# pedal.net
KiCad netlist of a schematic drawn in Altium Designer
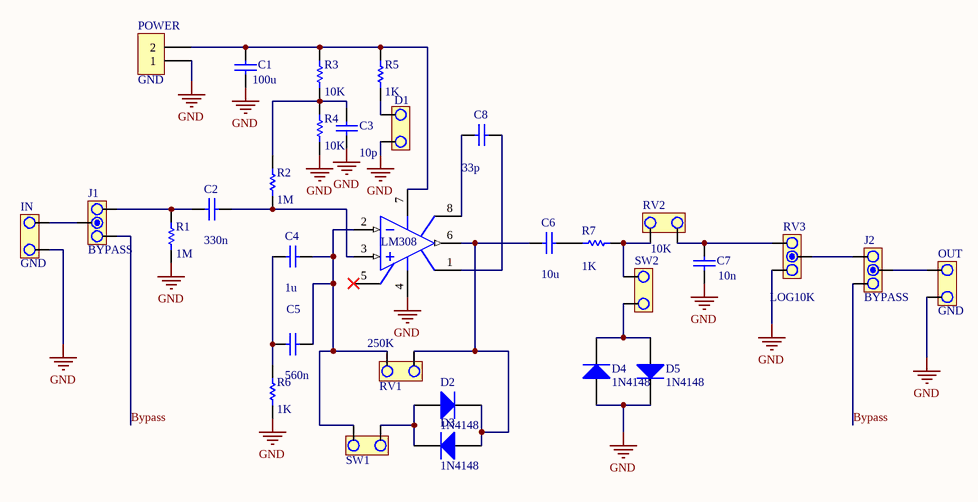
[diagram p0: pedal.SchDoc]

(export (version "E")
  (design (tool "Eeschema 10.0.6"))
  (components
    (comp (ref "C1")
      (value "100u")
      (footprint "CAP200")
      (description "Capacitor")
      (fields (field (name "PUBLISHER") "Altium Limited"))
      (libsource (lib "Miscellaneous Devices") (part "Cap"))
    )
    (comp (ref "C2")
      (value "330n")
      (footprint "CAP200")
      (description "Capacitor")
      (fields (field (name "PUBLISHER") "Altium Limited"))
      (libsource (lib "Miscellaneous Devices") (part "Cap"))
    )
    (comp (ref "C3")
      (value "10p")
      (footprint "CAP200")
      (description "Capacitor")
      (fields (field (name "PUBLISHER") "Altium Limited"))
      (libsource (lib "Miscellaneous Devices") (part "Cap"))
    )
    (comp (ref "C4")
      (value "1u")
      (footprint "CAP200")
      (description "Capacitor")
      (fields (field (name "PUBLISHER") "Altium Limited"))
      (libsource (lib "Miscellaneous Devices") (part "Cap"))
    )
    (comp (ref "C5")
      (value "560n")
      (footprint "RAD-0.3")
      (description "Capacitor")
      (fields (field (name "PUBLISHER") "Altium Limited"))
      (libsource (lib "Miscellaneous Devices") (part "Cap"))
    )
    (comp (ref "C6")
      (value "10u")
      (footprint "CAP200")
      (description "Capacitor")
      (fields (field (name "PUBLISHER") "Altium Limited"))
      (libsource (lib "Miscellaneous Devices") (part "Cap"))
    )
    (comp (ref "C7")
      (value "10n")
      (footprint "CAP200")
      (description "Capacitor")
      (fields (field (name "PUBLISHER") "Altium Limited"))
      (libsource (lib "Miscellaneous Devices") (part "Cap"))
    )
    (comp (ref "C8")
      (value "33p")
      (footprint "CAP200")
      (fields (field (name "PUBLISHER") "Altium Limited"))
      (libsource (lib "Miscellaneous Devices") (part "Cap"))
    )
    (comp (ref "D1") (value "~") (footprint "JUMPER2") (libsource (lib "") (part "JUMPER_1")))
    (comp (ref "D2")
      (value "1N4148")
      (footprint "DO-35")
      (description "High Conductance Fast Diode")
      (fields (field (name "PUBLISHER") "Altium Limited"))
      (libsource (lib "Miscellaneous Devices") (part "Diode 1N4148"))
    )
    (comp (ref "D3")
      (value "1N4148")
      (footprint "DO-35")
      (description "High Conductance Fast Diode")
      (fields (field (name "PUBLISHER") "Altium Limited"))
      (libsource (lib "Miscellaneous Devices") (part "Diode 1N4148"))
    )
    (comp (ref "D4")
      (value "1N4148")
      (footprint "DO-35")
      (description "High Conductance Fast Diode")
      (fields (field (name "PUBLISHER") "Altium Limited"))
      (libsource (lib "Miscellaneous Devices") (part "Diode 1N4148"))
    )
    (comp (ref "D5")
      (value "1N4148")
      (footprint "DO-35")
      (description "High Conductance Fast Diode")
      (fields (field (name "PUBLISHER") "Altium Limited"))
      (libsource (lib "Miscellaneous Devices") (part "Diode 1N4148"))
    )
    (comp (ref "IN") (value "GND") (footprint "JUMPER2") (libsource (lib "LIB PIO IX") (part "JUMPER")))
    (comp (ref "J1") (value "BYPASS") (footprint "JUMPER3") (libsource (lib "LIB PIO IX") (part "JUMPER3")))
    (comp (ref "J2") (value "BYPASS") (footprint "JUMPER3") (libsource (lib "") (part "JUMPER3_1")))
    (comp (ref "LM308")
      (value "~")
      (footprint "DIP8")
      (description "FET Operational Amplifier")
      (fields (field (name "PUBLISHER") "Altium Limited"))
      (libsource (lib "Miscellaneous Devices") (part "Op Amp"))
    )
    (comp (ref "OUT") (value "GND") (footprint "JUMPER2") (libsource (lib "") (part "JUMPER_1")))
    (comp (ref "POWER")
      (value "GND")
      (footprint "BORNERA2")
      (libsource (lib "LIB PIO IX") (part "BORNERA 2"))
    )
    (comp (ref "R1")
      (value "1M")
      (footprint "AXIAL-0.3")
      (description "Resistor")
      (fields (field (name "PUBLISHER") "Altium Limited"))
      (libsource (lib "Miscellaneous Devices") (part "Res1"))
    )
    (comp (ref "R2")
      (value "1M")
      (footprint "AXIAL-0.3")
      (description "Resistor")
      (fields (field (name "PUBLISHER") "Altium Limited"))
      (libsource (lib "Miscellaneous Devices") (part "Res1"))
    )
    (comp (ref "R3")
      (value "10K")
      (footprint "AXIAL-0.3")
      (description "Resistor")
      (fields (field (name "PUBLISHER") "Altium Limited"))
      (libsource (lib "Miscellaneous Devices") (part "Res1"))
    )
    (comp (ref "R4")
      (value "10K")
      (footprint "AXIAL-0.3")
      (description "Resistor")
      (fields (field (name "PUBLISHER") "Altium Limited"))
      (libsource (lib "Miscellaneous Devices") (part "Res1"))
    )
    (comp (ref "R5")
      (value "1K")
      (footprint "AXIAL-0.3")
      (description "Resistor")
      (fields (field (name "PUBLISHER") "Altium Limited"))
      (libsource (lib "Miscellaneous Devices") (part "Res1"))
    )
    (comp (ref "R6")
      (value "1K")
      (footprint "AXIAL-0.3")
      (description "Resistor")
      (fields (field (name "PUBLISHER") "Altium Limited"))
      (libsource (lib "Miscellaneous Devices") (part "Res1"))
    )
    (comp (ref "R7")
      (value "1K")
      (footprint "AXIAL-0.3")
      (description "Resistor")
      (fields (field (name "PUBLISHER") "Altium Limited"))
      (libsource (lib "Miscellaneous Devices") (part "Res1"))
    )
    (comp (ref "RV1") (value "250K") (footprint "JUMPER2") (libsource (lib "") (part "JUMPER_3")))
    (comp (ref "RV2") (value "10K") (footprint "JUMPER2") (libsource (lib "") (part "JUMPER_2")))
    (comp (ref "RV3") (value "LOG10K") (footprint "JUMPER3") (libsource (lib "") (part "JUMPER3_1")))
    (comp (ref "SW1") (value "~") (footprint "JUMPER2") (libsource (lib "") (part "JUMPER_3")))
    (comp (ref "SW2") (value "~") (footprint "JUMPER2") (libsource (lib "") (part "JUMPER_1")))
  )
  (nets
    (net (code "1") (name "/Bypass") (class "Default")
      (node (ref "J1") (pin "3") (pinfunction "3_3") (pintype "passive"))
      (node (ref "J2") (pin "1") (pinfunction "1_1") (pintype "passive"))
    )
    (net (code "2") (name "GND") (class "Default")
      (node (ref "C1") (pin "1") (pinfunction "1_1") (pintype "passive"))
      (node (ref "C3") (pin "1") (pinfunction "1_1") (pintype "passive"))
      (node (ref "C7") (pin "1") (pinfunction "1_1") (pintype "passive"))
      (node (ref "D1") (pin "1") (pinfunction "1_1") (pintype "passive"))
      (node (ref "D4") (pin "1") (pinfunction "A_1") (pintype "passive"))
      (node (ref "D5") (pin "2") (pinfunction "K_2") (pintype "passive"))
      (node (ref "IN") (pin "2") (pinfunction "2_2") (pintype "passive"))
      (node (ref "LM308") (pin "4") (pinfunction "V-_4") (pintype "power_in"))
      (node (ref "OUT") (pin "1") (pinfunction "1_1") (pintype "passive"))
      (node (ref "POWER") (pin "1") (pinfunction "1_1") (pintype "passive"))
      (node (ref "R1") (pin "1") (pinfunction "1_1") (pintype "passive"))
      (node (ref "R4") (pin "1") (pinfunction "1_1") (pintype "passive"))
      (node (ref "R6") (pin "1") (pinfunction "1_1") (pintype "passive"))
      (node (ref "RV3") (pin "1") (pinfunction "1_1") (pintype "passive"))
    )
    (net (code "3") (name "Net-(C2-Pad1)") (class "Default")
      (node (ref "C2") (pin "1") (pinfunction "1_1") (pintype "passive"))
      (node (ref "J1") (pin "1") (pinfunction "1_1") (pintype "passive"))
      (node (ref "R1") (pin "2") (pinfunction "2_2") (pintype "passive"))
    )
    (net (code "4") (name "Net-(C3-Pad2)") (class "Default")
      (node (ref "C3") (pin "2") (pinfunction "2_2") (pintype "passive"))
      (node (ref "R2") (pin "2") (pinfunction "2_2") (pintype "passive"))
      (node (ref "R3") (pin "1") (pinfunction "1_1") (pintype "passive"))
      (node (ref "R4") (pin "2") (pinfunction "2_2") (pintype "passive"))
    )
    (net (code "5") (name "Net-(C4-Pad1)") (class "Default")
      (node (ref "C4") (pin "1") (pinfunction "1_1") (pintype "passive"))
      (node (ref "C5") (pin "1") (pinfunction "1_1") (pintype "passive"))
      (node (ref "R6") (pin "2") (pinfunction "2_2") (pintype "passive"))
    )
    (net (code "6") (name "Net-(C6-Pad2)") (class "Default")
      (node (ref "C6") (pin "2") (pinfunction "2_2") (pintype "passive"))
      (node (ref "R7") (pin "1") (pinfunction "1_1") (pintype "passive"))
    )
    (net (code "7") (name "Net-(C7-Pad2)") (class "Default")
      (node (ref "C7") (pin "2") (pinfunction "2_2") (pintype "passive"))
      (node (ref "RV2") (pin "1") (pinfunction "1_1") (pintype "passive"))
      (node (ref "RV3") (pin "3") (pinfunction "3_3") (pintype "passive"))
    )
    (net (code "8") (name "Net-(C8-Pad2)") (class "Default")
      (node (ref "C8") (pin "2") (pinfunction "2_2") (pintype "passive"))
      (node (ref "LM308") (pin "1") (pinfunction "OS_NUL_1") (pintype "passive"))
    )
    (net (code "9") (name "Net-(D1-Pad2)") (class "Default")
      (node (ref "D1") (pin "2") (pinfunction "2_2") (pintype "passive"))
      (node (ref "R5") (pin "1") (pinfunction "1_1") (pintype "passive"))
    )
    (net (code "10") (name "Net-(D2-A)") (class "Default")
      (node (ref "D2") (pin "1") (pinfunction "A_1") (pintype "passive"))
      (node (ref "D3") (pin "2") (pinfunction "K_2") (pintype "passive"))
      (node (ref "SW1") (pin "2") (pinfunction "2_2") (pintype "passive"))
    )
    (net (code "11") (name "Net-(D2-K)") (class "Default")
      (node (ref "C6") (pin "1") (pinfunction "1_1") (pintype "passive"))
      (node (ref "D2") (pin "2") (pinfunction "K_2") (pintype "passive"))
      (node (ref "D3") (pin "1") (pinfunction "A_1") (pintype "passive"))
      (node (ref "LM308") (pin "6") (pinfunction "OUT_6") (pintype "output"))
      (node (ref "RV1") (pin "2") (pinfunction "2_2") (pintype "passive"))
    )
    (net (code "12") (name "Net-(D4-K)") (class "Default")
      (node (ref "D4") (pin "2") (pinfunction "K_2") (pintype "passive"))
      (node (ref "D5") (pin "1") (pinfunction "A_1") (pintype "passive"))
      (node (ref "SW2") (pin "1") (pinfunction "1_1") (pintype "passive"))
    )
    (net (code "13") (name "Net-(IN-Pad1)") (class "Default")
      (node (ref "IN") (pin "1") (pinfunction "1_1") (pintype "passive"))
      (node (ref "J1") (pin "2") (pinfunction "2_2") (pintype "passive"))
    )
    (net (code "14") (name "Net-(J2-Pad2)") (class "Default")
      (node (ref "J2") (pin "2") (pinfunction "2_2") (pintype "passive"))
      (node (ref "OUT") (pin "2") (pinfunction "2_2") (pintype "passive"))
    )
    (net (code "15") (name "Net-(J2-Pad3)") (class "Default")
      (node (ref "J2") (pin "3") (pinfunction "3_3") (pintype "passive"))
      (node (ref "RV3") (pin "2") (pinfunction "2_2") (pintype "passive"))
    )
    (net (code "16") (name "Net-(LM308-IN+)") (class "Default")
      (node (ref "C2") (pin "2") (pinfunction "2_2") (pintype "passive"))
      (node (ref "LM308") (pin "3") (pinfunction "IN+_3") (pintype "input"))
      (node (ref "R2") (pin "1") (pinfunction "1_1") (pintype "passive"))
    )
    (net (code "17") (name "Net-(LM308-IN-)") (class "Default")
      (node (ref "C4") (pin "2") (pinfunction "2_2") (pintype "passive"))
      (node (ref "C5") (pin "2") (pinfunction "2_2") (pintype "passive"))
      (node (ref "LM308") (pin "2") (pinfunction "IN-_2") (pintype "input"))
      (node (ref "RV1") (pin "1") (pinfunction "1_1") (pintype "passive"))
      (node (ref "SW1") (pin "1") (pinfunction "1_1") (pintype "passive"))
    )
    (net (code "18") (name "Net-(LM308-TAB)") (class "Default")
      (node (ref "C8") (pin "1") (pinfunction "1_1") (pintype "passive"))
      (node (ref "LM308") (pin "8") (pinfunction "TAB_8") (pintype "passive"))
    )
    (net (code "19") (name "Net-(LM308-V+)") (class "Default")
      (node (ref "C1") (pin "2") (pinfunction "2_2") (pintype "passive"))
      (node (ref "LM308") (pin "7") (pinfunction "V+_7") (pintype "power_in"))
      (node (ref "POWER") (pin "2") (pinfunction "2_2") (pintype "passive"))
      (node (ref "R3") (pin "2") (pinfunction "2_2") (pintype "passive"))
      (node (ref "R5") (pin "2") (pinfunction "2_2") (pintype "passive"))
    )
    (net (code "20") (name "Net-(R7-Pad2)") (class "Default")
      (node (ref "R7") (pin "2") (pinfunction "2_2") (pintype "passive"))
      (node (ref "RV2") (pin "2") (pinfunction "2_2") (pintype "passive"))
      (node (ref "SW2") (pin "2") (pinfunction "2_2") (pintype "passive"))
    )
    (net (code "21") (name "unconnected-(LM308-OS_NUL-Pad5)") (class "Default")
      (node (ref "LM308") (pin "5") (pinfunction "OS_NUL_5") (pintype "passive+no_connect"))
    )
  )
)
